# power-v5v5.net
KiCad netlist of a schematic drawn in Altium Designer
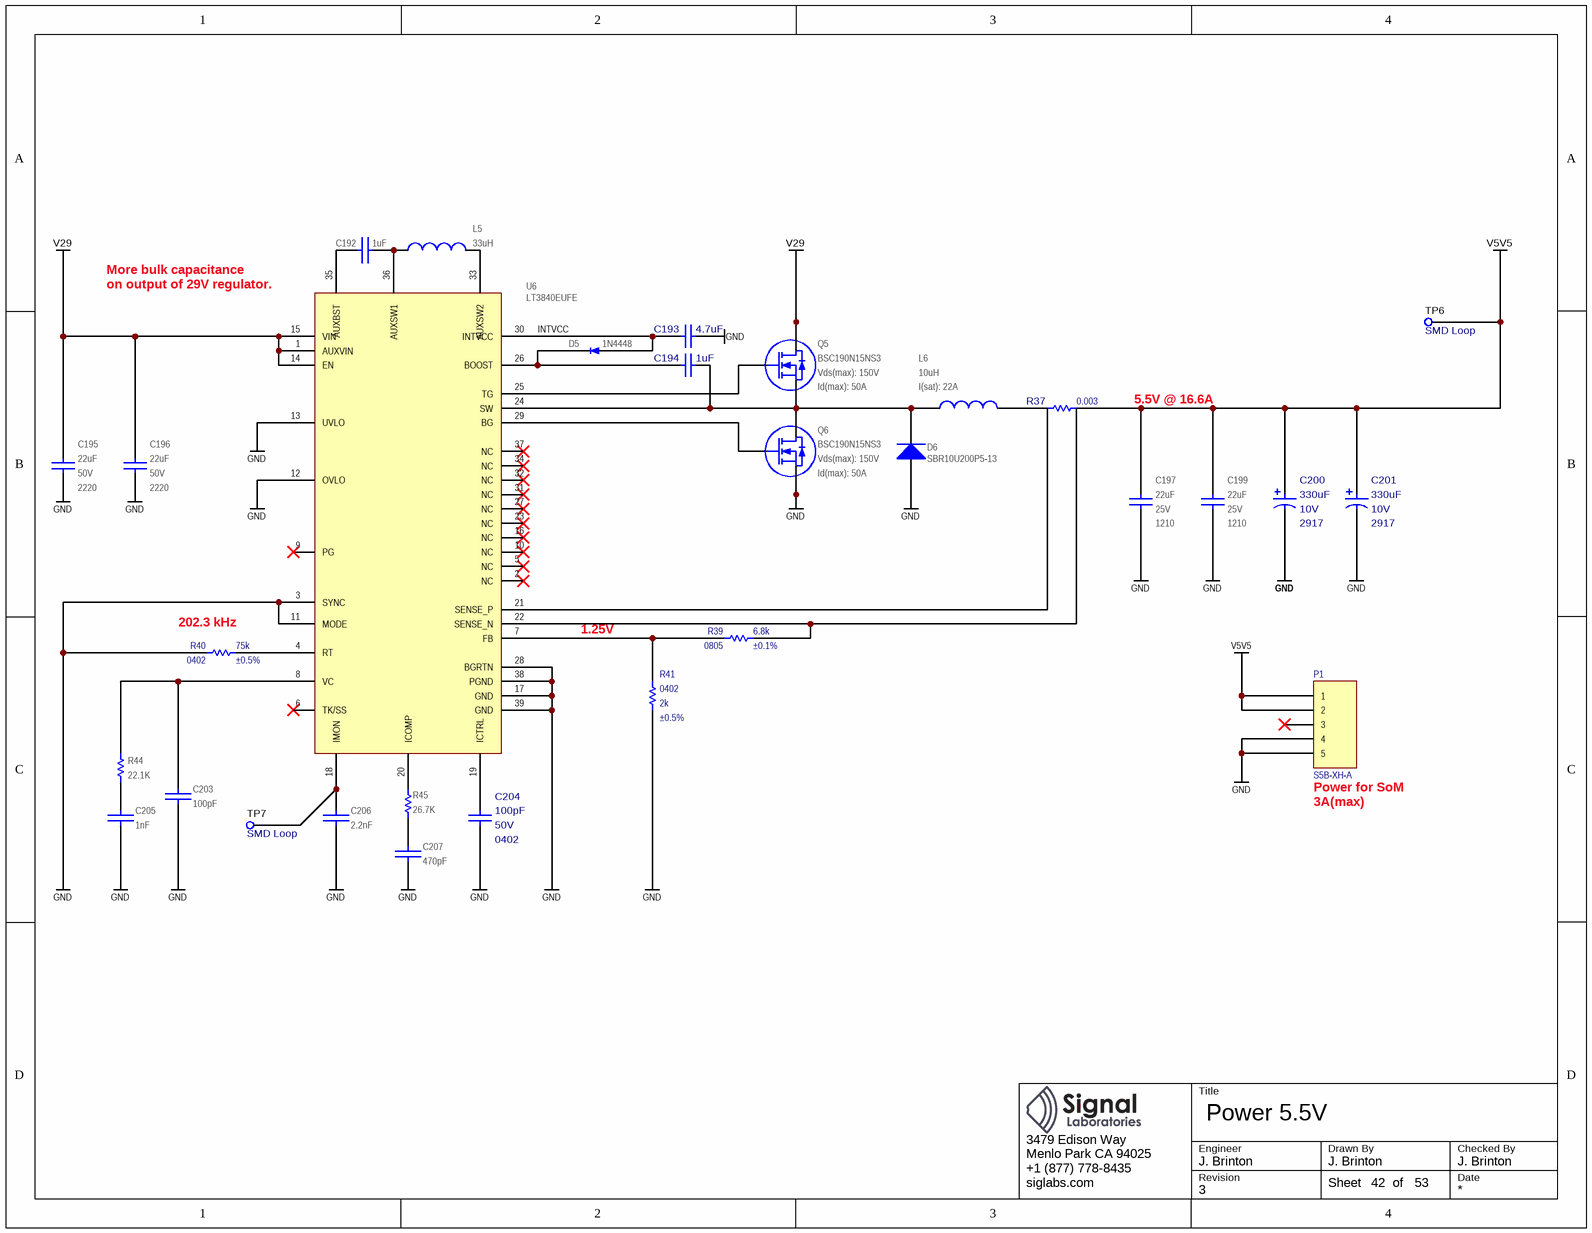
[diagram p0: power-v5v5.SchDoc]

(export (version "E")
  (design (tool "Eeschema 10.0.6"))
  (components
    (comp (ref "C192")
      (value "1uF")
      (footprint "CAPC100X50X55L25N")
      (description "Ceramic Capacitor 1uF ±10% 10V X5R 0402")
      (fields (field (name "MANUFACTURER") "Murata") (field (name "TOLERANCE") "±10%"))
      (libsource (lib "*") (part "CAP"))
    )
    (comp (ref "C193")
      (value "4.7uF")
      (footprint "CAPC160X80X90L20N")
      (description "Ceramic Capacitor 4.7uF ±10% 25V X5R 0603")
      (fields (field (name "MANUFACTURER") "Samsung") (field (name "TOLERANCE") "±10%"))
      (libsource (lib "capacitors") (part "CAP"))
    )
    (comp (ref "C194")
      (value "1uF")
      (footprint "CAPC100X50X55L25N")
      (description "Ceramic Capacitor 1uF ±10% 10V X5R 0402")
      (fields (field (name "MANUFACTURER") "Murata") (field (name "TOLERANCE") "±10%"))
      (libsource (lib "capacitors") (part "CAP"))
    )
    (comp (ref "C195")
      (value "22uF")
      (footprint "CAPC600X500X500L160N")
      (description "Ceramic Capacitor 22uF ±20% 50V X7S Stacked")
      (fields
        (field (name "MANUFACTURER") "TDK")
        (field (name "TOLERANCE") "±20%")
        (field (name "VOLTAGE") "50V")
        (field (name "PACKAGE") "2220")
      )
      (libsource (lib "generic") (part "CAP"))
    )
    (comp (ref "C196")
      (value "22uF")
      (footprint "CAPC600X500X500L160N")
      (description "Ceramic Capacitor 22uF ±20% 50V X7S Stacked")
      (fields
        (field (name "MANUFACTURER") "TDK")
        (field (name "TOLERANCE") "±20%")
        (field (name "VOLTAGE") "50V")
        (field (name "PACKAGE") "2220")
      )
      (libsource (lib "generic") (part "CAP"))
    )
    (comp (ref "C197")
      (value "22uF")
      (footprint "CAPC320X250X270L50N")
      (description "Ceramic Capacitor 22uF ±10% 25V X7R 1210")
      (fields
        (field (name "MANUFACTURER") "Murata")
        (field (name "TOLERANCE") "±10%")
        (field (name "VOLTAGE") "25V")
        (field (name "PACKAGE") "1210")
      )
      (libsource (lib "generic") (part "CAP"))
    )
    (comp (ref "C199")
      (value "22uF")
      (footprint "CAPC320X250X270L50N")
      (description "Ceramic Capacitor 22uF ±10% 25V X7R 1210")
      (fields
        (field (name "MANUFACTURER") "Murata")
        (field (name "TOLERANCE") "±10%")
        (field (name "VOLTAGE") "25V")
        (field (name "PACKAGE") "1210")
      )
      (libsource (lib "generic") (part "CAP"))
    )
    (comp (ref "C200")
      (value "330uF")
      (footprint "CAPPM730X435X310L135X240N")
      (description "Tantalum Capacitor 330uF ±10% 10V 2917")
      (fields
        (field (name "MANUFACTURER") "AVX")
        (field (name "TOLERANCE") "±10%")
        (field (name "PACKAGE") "2917")
        (field (name "VOLTAGE") "10V")
      )
      (libsource (lib "avx") (part "CAP_POL"))
    )
    (comp (ref "C201")
      (value "330uF")
      (footprint "CAPPM730X435X310L135X240N")
      (description "Tantalum Capacitor 330uF ±10% 10V 2917")
      (fields
        (field (name "MANUFACTURER") "AVX")
        (field (name "TOLERANCE") "±10%")
        (field (name "PACKAGE") "2917")
        (field (name "VOLTAGE") "10V")
      )
      (libsource (lib "avx") (part "CAP_POL"))
    )
    (comp (ref "C203")
      (value "100pF")
      (footprint "CAPC100X50X55L25N")
      (description "Ceramic Capacitor 100pF ±5% 50V NP0 0402")
      (fields (field (name "MANUFACTURER") "Murata") (field (name "VOLTAGE") "50V"))
      (libsource (lib "*") (part "CAP"))
    )
    (comp (ref "C204")
      (value "100pF")
      (footprint "generic:CAPC100X50X55L25N")
      (description "Ceramic Capacitor 100pF ±10% 50V C0G 0402")
      (fields
        (field (name "MANUFACTURER") "Vishay")
        (field (name "TOLERANCE") "±10%")
        (field (name "PACKAGE") "0402")
        (field (name "VOLTAGE") "50V")
      )
      (libsource (lib "capacitors") (part "CAP"))
    )
    (comp (ref "C205")
      (value "1nF")
      (footprint "CAPC100X50X55L25N")
      (description "Ceramic Capacitor 1nF ±5% 50V NP0 0402")
      (fields (field (name "MANUFACTURER") "Murata") (field (name "VOLTAGE") "50V"))
      (libsource (lib "*") (part "CAP"))
    )
    (comp (ref "C206")
      (value "2.2nF")
      (footprint "CAPC100X50X55L25N")
      (description "Ceramic Capacitor 2.2nF ±5% 25V NP0 0402")
      (fields (field (name "MANUFACTURER") "Kemet") (field (name "TOLERANCE") "±5%"))
      (libsource (lib "*") (part "CAP"))
    )
    (comp (ref "C207")
      (value "470pF")
      (footprint "CAPC100X50X55L25N")
      (description "Ceramic Capacitor 470pF ±5% 50V X7R 0402")
      (fields (field (name "MANUFACTURER") "Murata") (field (name "VOLTAGE") "50V"))
      (libsource (lib "*") (part "CAP"))
    )
    (comp (ref "D5")
      (value "1N4448HWS-7-F")
      (footprint "diodes_inc:SOD323")
      (description "Schottky Diode 80V 250mA SOD323")
      (fields (field (name "MANUFACTURER") "Diodes Inc") (field (name "ALTERNATIVE P/N") "1N4448"))
      (libsource (lib "diodes_inc") (part "1N4448HWS-7-F"))
    )
    (comp (ref "D6")
      (value "SBR10U200P5-13")
      (footprint "DIODES_POWERDI5")
      (description "Schottky Diode 200V 10A SMD")
      (fields (field (name "MANUFACTURER") "Diodes Inc"))
      (libsource (lib "diodes_inc") (part "PDS5100H"))
    )
    (comp (ref "L5")
      (value "33uH")
      (footprint "coilcraft:ME3220")
      (description "Inductor 33uH ±10% 500mA SMD")
      (fields (field (name "MANUFACTURER") "Coilcraft") (field (name "TOLERANCE") "±10%"))
      (libsource (lib "CamBoard_Pico_70.19K") (part "COIL"))
    )
    (comp (ref "L6")
      (value "10uH")
      (footprint "HCM1A1707")
      (description "Inductor 10uH, 22A(sat), SMD")
      (fields
        (field (name "MANUFACTURER") "Pulse Electronics Power")
        (field (name "I(SAT)") "22A")
        (field (name "Comment") "PA4344.103ANLT")
      )
      (libsource (lib "CamBoard_Pico_70.19K") (part "COIL"))
    )
    (comp (ref "P1")
      (value "S5B-XH-A")
      (footprint "jst:S5B-XH-A")
      (description "2.5mm pitch right angle 5-position")
      (fields (field (name "MANUFACTURER") "JST"))
      (libsource (lib "jst") (part "S5B-XH-A"))
    )
    (comp (ref "Q5")
      (value "BSC190N15NS3")
      (footprint "TDSON-8")
      (description "MOSFET N-Channel Enhancement Mode")
      (fields
        (field (name "MANUFACTURER") "Infineon")
        (field (name "VDS(MAX)") "150V")
        (field (name "ID(MAX)") "50A")
      )
      (libsource (lib "infinion") (part "BSC190N15NS3"))
    )
    (comp (ref "Q6")
      (value "BSC190N15NS3")
      (footprint "TDSON-8")
      (description "MOSFET N-Channel Enhancement Mode")
      (fields
        (field (name "MANUFACTURER") "Infineon")
        (field (name "VDS(MAX)") "150V")
        (field (name "ID(MAX)") "50A")
      )
      (libsource (lib "infinion") (part "BSC190N15NS3"))
    )
    (comp (ref "R37")
      (value "0.003")
      (footprint "susumu:KRL3216T4")
      (description "Current Sense Resistor 3 mOhms +/-1% SMD 4-Terminal")
      (fields (field (name "TOLERANCE") "±1%") (field (name "MANUFACTURER") "Susumu"))
      (libsource (lib "susumu") (part "KRL3216T4A-M-R009-F"))
    )
    (comp (ref "R39")
      (value "6.8k")
      (footprint "RESC2012X70N")
      (description "Thin Film Resistor 6.8k +/-0.1% SMD 0805")
      (fields
        (field (name "TOLERANCE") "±0.1%")
        (field (name "MANUFACTURER") "Susumu")
        (field (name "PACKAGE") "0805")
        (field (name "Comment") "RG2012P-682-B-T5")
      )
      (libsource (lib "generic") (part "RES"))
    )
    (comp (ref "R40")
      (value "75k")
      (footprint "RESC1005X40N")
      (description "Thin Film Resistor 75k +/-0.5% SMD 0402")
      (fields
        (field (name "TOLERANCE") "±0.5%")
        (field (name "MANUFACTURER") "Susumu")
        (field (name "PACKAGE") "0402")
        (field (name "Comment") "RR0510P-753-D")
      )
      (libsource (lib "generic") (part "RES"))
    )
    (comp (ref "R41")
      (value "2k")
      (footprint "RESC1005X40N")
      (description "Thin Film Resistor 2k +/-0.5% SMD 0402")
      (fields
        (field (name "TOLERANCE") "±0.5%")
        (field (name "MANUFACTURER") "Susumu")
        (field (name "PACKAGE") "0402")
        (field (name "Comment") "RR0510P-202-D")
      )
      (libsource (lib "generic") (part "RES"))
    )
    (comp (ref "R44")
      (value "22.1K")
      (footprint "generic:RESC1005X40N")
      (description "Thick Film Resistor 22.1k ±1% 0402")
      (fields (field (name "MANUFACTURER") "Panasonic") (field (name "TOLERANCE") "±1%"))
      (libsource (lib "Graviton") (part "RES 0402"))
    )
    (comp (ref "R45")
      (value "26.7K")
      (footprint "generic:RESC1005X40N")
      (description "Thick Film Resistor 26.7k ±1% 0402")
      (fields (field (name "MANUFACTURER") "Panasonic") (field (name "TOLERANCE") "±1%"))
      (libsource (lib "Graviton") (part "RES 0402"))
    )
    (comp (ref "TP6")
      (value "5015")
      (footprint "keystone:5015")
      (description "Test Point SMD")
      (fields (field (name "MANUFACTURER") "Keystone") (field (name "NOTES") "SMD Loop"))
      (libsource (lib "generic") (part "TEST_POINT_SMD_50"))
    )
    (comp (ref "TP7")
      (value "5015")
      (footprint "keystone:5015")
      (description "Test Point SMD")
      (fields (field (name "MANUFACTURER") "Keystone") (field (name "NOTES") "SMD Loop"))
      (libsource (lib "generic") (part "TEST_POINT_SMD_50"))
    )
    (comp (ref "U6")
      (value "LT3840EUFE")
      (footprint "linear:QFN39P40_600X400X80L40X20T465X265N")
      (description "Synchronous Regulator Controller")
      (fields (field (name "MANUFACTURER") "Linear Technology"))
      (libsource (lib "linear") (part "LT3840EUFE"))
    )
  )
  (nets
    (net (code "1") (name "/INTVCC") (class "Default")
      (node (ref "C193") (pin "1") (pinfunction "1_1") (pintype "passive"))
      (node (ref "D5") (pin "A") (pinfunction "A_A") (pintype "passive"))
      (node (ref "U6") (pin "30") (pinfunction "INTVCC_30") (pintype "passive"))
    )
    (net (code "2") (name "GND") (class "Default")
      (node (ref "C193") (pin "2") (pinfunction "2_2") (pintype "passive"))
      (node (ref "C195") (pin "1") (pinfunction "1_1") (pintype "passive"))
      (node (ref "C196") (pin "1") (pinfunction "1_1") (pintype "passive"))
      (node (ref "C197") (pin "1") (pinfunction "1_1") (pintype "passive"))
      (node (ref "C199") (pin "1") (pinfunction "1_1") (pintype "passive"))
      (node (ref "C200") (pin "2") (pinfunction "2_2") (pintype "passive"))
      (node (ref "C201") (pin "2") (pinfunction "2_2") (pintype "passive"))
      (node (ref "C203") (pin "1") (pinfunction "1_1") (pintype "passive"))
      (node (ref "C204") (pin "2") (pinfunction "2_2") (pintype "passive"))
      (node (ref "C205") (pin "2") (pinfunction "2_2") (pintype "passive"))
      (node (ref "C206") (pin "2") (pinfunction "2_2") (pintype "passive"))
      (node (ref "C207") (pin "1") (pinfunction "1_1") (pintype "passive"))
      (node (ref "D6") (pin "A") (pinfunction "A_A") (pintype "power_in"))
      (node (ref "P1") (pin "4") (pinfunction "4_4") (pintype "passive"))
      (node (ref "P1") (pin "5") (pinfunction "5_5") (pintype "passive"))
      (node (ref "Q6") (pin "1") (pinfunction "S_1") (pintype "passive"))
      (node (ref "Q6") (pin "2") (pinfunction "S_2") (pintype "passive"))
      (node (ref "Q6") (pin "3") (pinfunction "S_3") (pintype "passive"))
      (node (ref "R40") (pin "2") (pinfunction "2_2") (pintype "passive"))
      (node (ref "R41") (pin "1") (pinfunction "1_1") (pintype "passive"))
      (node (ref "U6") (pin "11") (pinfunction "MODE_11") (pintype "passive"))
      (node (ref "U6") (pin "12") (pinfunction "OVLO_12") (pintype "passive"))
      (node (ref "U6") (pin "13") (pinfunction "UVLO_13") (pintype "passive"))
      (node (ref "U6") (pin "17") (pinfunction "GND_17") (pintype "passive"))
      (node (ref "U6") (pin "28") (pinfunction "BGRTN_28") (pintype "passive"))
      (node (ref "U6") (pin "3") (pinfunction "SYNC_3") (pintype "passive"))
      (node (ref "U6") (pin "38") (pinfunction "PGND_38") (pintype "passive"))
      (node (ref "U6") (pin "39") (pinfunction "GND_39") (pintype "passive"))
    )
    (net (code "3") (name "Net-(C205-Pad1)") (class "Default")
      (node (ref "C205") (pin "1") (pinfunction "1_1") (pintype "passive"))
      (node (ref "R44") (pin "1") (pinfunction "1_1") (pintype "passive"))
    )
    (net (code "4") (name "Net-(C207-Pad2)") (class "Default")
      (node (ref "C207") (pin "2") (pinfunction "2_2") (pintype "passive"))
      (node (ref "R45") (pin "2") (pinfunction "2_2") (pintype "passive"))
    )
    (net (code "5") (name "Net-(L6-Pad2)") (class "Default")
      (node (ref "L6") (pin "2") (pinfunction "2_2") (pintype "passive"))
      (node (ref "R37") (pin "2") (pinfunction "2_2") (pintype "passive"))
    )
    (net (code "6") (name "Net-(Q5-G)") (class "Default")
      (node (ref "Q5") (pin "4") (pinfunction "G_4") (pintype "passive"))
      (node (ref "U6") (pin "25") (pinfunction "TG_25") (pintype "passive"))
    )
    (net (code "7") (name "Net-(Q6-G)") (class "Default")
      (node (ref "Q6") (pin "4") (pinfunction "G_4") (pintype "passive"))
      (node (ref "U6") (pin "29") (pinfunction "BG_29") (pintype "passive"))
    )
    (net (code "8") (name "Net-(U6-AUXBST)") (class "Default")
      (node (ref "C192") (pin "2") (pinfunction "2_2") (pintype "passive"))
      (node (ref "U6") (pin "35") (pinfunction "AUXBST_35") (pintype "passive"))
    )
    (net (code "9") (name "Net-(U6-AUXSW1)") (class "Default")
      (node (ref "C192") (pin "1") (pinfunction "1_1") (pintype "passive"))
      (node (ref "L5") (pin "1") (pinfunction "1_1") (pintype "passive"))
      (node (ref "U6") (pin "36") (pinfunction "AUXSW1_36") (pintype "passive"))
    )
    (net (code "10") (name "Net-(U6-AUXSW2)") (class "Default")
      (node (ref "L5") (pin "2") (pinfunction "2_2") (pintype "passive"))
      (node (ref "U6") (pin "33") (pinfunction "AUXSW2_33") (pintype "passive"))
    )
    (net (code "11") (name "Net-(U6-BOOST)") (class "Default")
      (node (ref "C194") (pin "1") (pinfunction "1_1") (pintype "passive"))
      (node (ref "D5") (pin "K") (pinfunction "K_K") (pintype "passive"))
      (node (ref "U6") (pin "26") (pinfunction "BOOST_26") (pintype "passive"))
    )
    (net (code "12") (name "Net-(U6-FB)") (class "Default")
      (node (ref "R39") (pin "2") (pinfunction "2_2") (pintype "passive"))
      (node (ref "R41") (pin "2") (pinfunction "2_2") (pintype "passive"))
      (node (ref "U6") (pin "7") (pinfunction "FB_7") (pintype "passive"))
    )
    (net (code "13") (name "Net-(U6-ICOMP)") (class "Default")
      (node (ref "R45") (pin "1") (pinfunction "1_1") (pintype "passive"))
      (node (ref "U6") (pin "20") (pinfunction "ICOMP_20") (pintype "passive"))
    )
    (net (code "14") (name "Net-(U6-ICTRL)") (class "Default")
      (node (ref "C204") (pin "1") (pinfunction "1_1") (pintype "passive"))
      (node (ref "U6") (pin "19") (pinfunction "ICTRL_19") (pintype "passive"))
    )
    (net (code "15") (name "Net-(U6-IMON)") (class "Default")
      (node (ref "C206") (pin "1") (pinfunction "1_1") (pintype "passive"))
      (node (ref "TP7") (pin "1") (pinfunction "1_1") (pintype "passive"))
      (node (ref "U6") (pin "18") (pinfunction "IMON_18") (pintype "passive"))
    )
    (net (code "16") (name "Net-(U6-RT)") (class "Default")
      (node (ref "R40") (pin "1") (pinfunction "1_1") (pintype "passive"))
      (node (ref "U6") (pin "4") (pinfunction "RT_4") (pintype "passive"))
    )
    (net (code "17") (name "Net-(U6-SENSE_N)") (class "Default")
      (node (ref "R37") (pin "3") (pinfunction "3_3") (pintype "passive"))
      (node (ref "R39") (pin "1") (pinfunction "1_1") (pintype "passive"))
      (node (ref "U6") (pin "22") (pinfunction "SENSE_N_22") (pintype "passive"))
    )
    (net (code "18") (name "Net-(U6-SENSE_P)") (class "Default")
      (node (ref "R37") (pin "4") (pinfunction "4_4") (pintype "passive"))
      (node (ref "U6") (pin "21") (pinfunction "SENSE_P_21") (pintype "passive"))
    )
    (net (code "19") (name "Net-(U6-SW)") (class "Default")
      (node (ref "C194") (pin "2") (pinfunction "2_2") (pintype "passive"))
      (node (ref "D6") (pin "K") (pinfunction "K_K") (pintype "passive"))
      (node (ref "L6") (pin "1") (pinfunction "1_1") (pintype "passive"))
      (node (ref "Q5") (pin "1") (pinfunction "S_1") (pintype "passive"))
      (node (ref "Q5") (pin "2") (pinfunction "S_2") (pintype "passive"))
      (node (ref "Q5") (pin "3") (pinfunction "S_3") (pintype "passive"))
      (node (ref "Q6") (pin "5") (pinfunction "D_5") (pintype "passive"))
      (node (ref "Q6") (pin "6") (pinfunction "D_6") (pintype "passive"))
      (node (ref "Q6") (pin "7") (pinfunction "D_7") (pintype "passive"))
      (node (ref "Q6") (pin "8") (pinfunction "D_8") (pintype "passive"))
      (node (ref "Q6") (pin "9") (pinfunction "D_9") (pintype "passive"))
      (node (ref "U6") (pin "24") (pinfunction "SW_24") (pintype "passive"))
    )
    (net (code "20") (name "Net-(U6-VC)") (class "Default")
      (node (ref "C203") (pin "2") (pinfunction "2_2") (pintype "passive"))
      (node (ref "R44") (pin "2") (pinfunction "2_2") (pintype "passive"))
      (node (ref "U6") (pin "8") (pinfunction "VC_8") (pintype "passive"))
    )
    (net (code "21") (name "V5V5") (class "Default")
      (node (ref "C197") (pin "2") (pinfunction "2_2") (pintype "passive"))
      (node (ref "C199") (pin "2") (pinfunction "2_2") (pintype "passive"))
      (node (ref "C200") (pin "1") (pinfunction "1_1") (pintype "passive"))
      (node (ref "C201") (pin "1") (pinfunction "1_1") (pintype "passive"))
      (node (ref "P1") (pin "1") (pinfunction "1_1") (pintype "passive"))
      (node (ref "P1") (pin "2") (pinfunction "2_2") (pintype "passive"))
      (node (ref "R37") (pin "1") (pinfunction "1_1") (pintype "passive"))
      (node (ref "TP6") (pin "1") (pinfunction "1_1") (pintype "passive"))
    )
    (net (code "22") (name "V29") (class "Default")
      (node (ref "C195") (pin "2") (pinfunction "2_2") (pintype "passive"))
      (node (ref "C196") (pin "2") (pinfunction "2_2") (pintype "passive"))
      (node (ref "Q5") (pin "5") (pinfunction "D_5") (pintype "passive"))
      (node (ref "Q5") (pin "6") (pinfunction "D_6") (pintype "passive"))
      (node (ref "Q5") (pin "7") (pinfunction "D_7") (pintype "passive"))
      (node (ref "Q5") (pin "8") (pinfunction "D_8") (pintype "passive"))
      (node (ref "Q5") (pin "9") (pinfunction "D_9") (pintype "passive"))
      (node (ref "U6") (pin "1") (pinfunction "AUXVIN_1") (pintype "passive"))
      (node (ref "U6") (pin "14") (pinfunction "EN_14") (pintype "passive"))
      (node (ref "U6") (pin "15") (pinfunction "VIN_15") (pintype "passive"))
    )
    (net (code "23") (name "unconnected-(P1-Pad3)") (class "Default")
      (node (ref "P1") (pin "3") (pinfunction "3_3") (pintype "passive+no_connect"))
    )
    (net (code "24") (name "unconnected-(U6-NC-Pad2)") (class "Default")
      (node (ref "U6") (pin "2") (pinfunction "NC_2") (pintype "passive+no_connect"))
    )
    (net (code "25") (name "unconnected-(U6-NC-Pad5)") (class "Default")
      (node (ref "U6") (pin "5") (pinfunction "NC_5") (pintype "passive+no_connect"))
    )
    (net (code "26") (name "unconnected-(U6-NC-Pad10)") (class "Default")
      (node (ref "U6") (pin "10") (pinfunction "NC_10") (pintype "passive+no_connect"))
    )
    (net (code "27") (name "unconnected-(U6-NC-Pad16)") (class "Default")
      (node (ref "U6") (pin "16") (pinfunction "NC_16") (pintype "passive+no_connect"))
    )
    (net (code "28") (name "unconnected-(U6-NC-Pad23)") (class "Default")
      (node (ref "U6") (pin "23") (pinfunction "NC_23") (pintype "passive+no_connect"))
    )
    (net (code "29") (name "unconnected-(U6-NC-Pad27)") (class "Default")
      (node (ref "U6") (pin "27") (pinfunction "NC_27") (pintype "passive+no_connect"))
    )
    (net (code "30") (name "unconnected-(U6-NC-Pad31)") (class "Default")
      (node (ref "U6") (pin "31") (pinfunction "NC_31") (pintype "passive+no_connect"))
    )
    (net (code "31") (name "unconnected-(U6-NC-Pad32)") (class "Default")
      (node (ref "U6") (pin "32") (pinfunction "NC_32") (pintype "passive+no_connect"))
    )
    (net (code "32") (name "unconnected-(U6-NC-Pad34)") (class "Default")
      (node (ref "U6") (pin "34") (pinfunction "NC_34") (pintype "passive+no_connect"))
    )
    (net (code "33") (name "unconnected-(U6-NC-Pad37)") (class "Default")
      (node (ref "U6") (pin "37") (pinfunction "NC_37") (pintype "passive+no_connect"))
    )
    (net (code "34") (name "unconnected-(U6-PG-Pad9)") (class "Default")
      (node (ref "U6") (pin "9") (pinfunction "PG_9") (pintype "passive+no_connect"))
    )
    (net (code "35") (name "unconnected-(U6-TK{slash}SS-Pad6)") (class "Default")
      (node (ref "U6") (pin "6") (pinfunction "TK/SS_6") (pintype "passive+no_connect"))
    )
  )
)
